# Back.net
KiCad netlist of a schematic drawn in Altium Designer
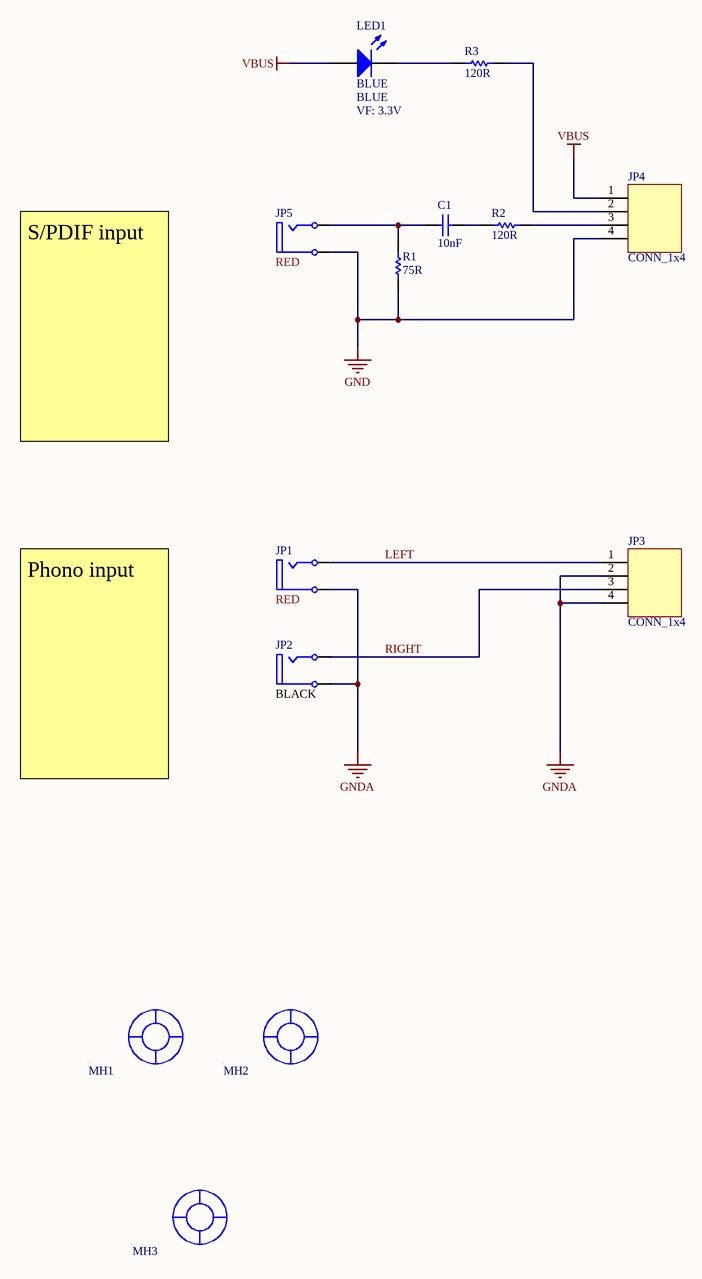
[diagram p0: Back.SchDoc]

(export (version "E")
  (design (tool "Eeschema 10.0.6"))
  (components
    (comp (ref "C1")
      (value "10nF")
      (footprint "CAPC0805(2012)145_N")
      (description "CAP 10nF 16V ±20% 0805 (2012 Metric) Thickness 1.45mm SMD")
      (fields (field (name "TOLERANCE") "Â±20%") (field (name "Comment") "CAP 10nF 16V 0805(2012)"))
      (libsource (lib "Altium Content Vault") (part "CAP"))
    )
    (comp (ref "JP1")
      (value "RED")
      (footprint "CONN_RCA-Lumberg-BTOR")
      (description "RCA panel-mount socket red, 1553 02 rot, Lumberg Connect GmbH")
      (fields (field (name "MPN") "BTOR 1 ROT") (field (name "Comment") "RCA RED"))
      (libsource (lib "micun") (part "CONN_RCA_LUMBERG_BTOR_1_RED"))
    )
    (comp (ref "JP2")
      (value "BLACK")
      (footprint "CONN_RCA-Lumberg-BTOR")
      (description "RCA panel-mount socket red, 1553 02 rot, Lumberg Connect GmbH")
      (fields (field (name "MPN") "BTOR 1 SCHWARZ") (field (name "Comment") "RCA BLACK"))
      (libsource (lib "micun") (part "CONN_RCA_LUMBERG_BTOR_1_BLACK"))
    )
    (comp (ref "JP3")
      (value "CONN_1x4")
      (footprint "CONN_HDR1X4-No3D")
      (description "Header, 4-Pin")
      (fields (field (name "MPN") "0470531000") (field (name "PUBLISHER") "Altium Limited"))
      (libsource (lib "micun") (part "CONN_MHDR_1x4"))
    )
    (comp (ref "JP4")
      (value "CONN_1x4")
      (footprint "CONN_HDR1X4-No3D")
      (description "Header, 4-Pin")
      (fields (field (name "MPN") "0470531000") (field (name "PUBLISHER") "Altium Limited"))
      (libsource (lib "micun") (part "CONN_MHDR_1x4"))
    )
    (comp (ref "JP5")
      (value "RED")
      (footprint "CONN_RCA-Lumberg-BTOR")
      (description "RCA panel-mount socket red, 1553 02 rot, Lumberg Connect GmbH")
      (fields (field (name "MPN") "BTOR 1 ROT") (field (name "Comment") "RCA RED"))
      (libsource (lib "micun") (part "CONN_RCA_LUMBERG_BTOR_1_RED"))
    )
    (comp (ref "LED1")
      (value "BLUE")
      (footprint "LED-KPTL-3216QBC")
      (description "LED BLUE")
      (fields
        (field (name "MPN") "KPTL-3216QBC-D-01")
        (field (name "ALTIUM_VALUE") "BLUE")
        (field (name "VF") "3.3V")
      )
      (libsource (lib "micun") (part "LED-BLUE-KPTL-3216QBC-D-01"))
    )
    (comp (ref "MH1")
      (value "Mounting hole")
      (footprint "MECH_MHOLE_3.5-GND")
      (libsource (lib "micun") (part "MECH_MHOLE"))
    )
    (comp (ref "MH2")
      (value "Mounting hole")
      (footprint "MECH_MHOLE_3.5")
      (libsource (lib "micun") (part "MECH_MHOLE"))
    )
    (comp (ref "MH3")
      (value "Mounting hole")
      (footprint "MECH_USB_MICRO_CUTOUT")
      (libsource (lib "micun") (part "MECH_MICRO_B_CUTOUT"))
    )
    (comp (ref "R1")
      (value "75R")
      (footprint "RESC0805(2012)_M")
      (description "75R 0.125W 1% 0805 (2012 Metric)  SMD")
      (fields (field (name "TOLERANCE") "1 %") (field (name "POWER") "0.125 W"))
      (libsource (lib "Altium Content Vault") (part "RES"))
    )
    (comp (ref "R2")
      (value "120R")
      (footprint "RESC0805(2012)_N")
      (description "120R 0.125W 5% 0805 (2012 Metric)  SMD")
      (fields (field (name "TOLERANCE") "5 %") (field (name "POWER") "0.125 W"))
      (libsource (lib "Altium Content Vault") (part "RES"))
    )
    (comp (ref "R3")
      (value "120R")
      (footprint "RESC0805(2012)_N")
      (description "120R 0.125W 5% 0805 (2012 Metric)  SMD")
      (fields (field (name "TOLERANCE") "5 %") (field (name "POWER") "0.125 W"))
      (libsource (lib "Altium Content Vault") (part "RES"))
    )
  )
  (nets
    (net (code "1") (name "/LEFT") (class "Default")
      (node (ref "JP1") (pin "1") (pinfunction "Signal_1") (pintype "passive"))
      (node (ref "JP3") (pin "1") (pinfunction "1_1") (pintype "passive"))
    )
    (net (code "2") (name "/RIGHT") (class "Default")
      (node (ref "JP2") (pin "1") (pinfunction "Signal_1") (pintype "passive"))
      (node (ref "JP3") (pin "3") (pinfunction "3_3") (pintype "passive"))
    )
    (net (code "3") (name "GND") (class "Default")
      (node (ref "JP4") (pin "4") (pinfunction "4_4") (pintype "passive"))
      (node (ref "JP5") (pin "2") (pinfunction "Ground_2") (pintype "power_in"))
      (node (ref "R1") (pin "2") (pinfunction "2_2") (pintype "passive"))
    )
    (net (code "4") (name "GNDA") (class "Default")
      (node (ref "JP1") (pin "2") (pinfunction "Ground_2") (pintype "power_in"))
      (node (ref "JP2") (pin "2") (pinfunction "Ground_2") (pintype "power_in"))
      (node (ref "JP3") (pin "2") (pinfunction "2_2") (pintype "passive"))
      (node (ref "JP3") (pin "4") (pinfunction "4_4") (pintype "passive"))
    )
    (net (code "5") (name "Net-(C1-Pad1)") (class "Default")
      (node (ref "C1") (pin "1") (pinfunction "1_1") (pintype "passive"))
      (node (ref "R2") (pin "2") (pinfunction "2_2") (pintype "passive"))
    )
    (net (code "6") (name "Net-(JP4-Pad2)") (class "Default")
      (node (ref "JP4") (pin "2") (pinfunction "2_2") (pintype "passive"))
      (node (ref "R3") (pin "1") (pinfunction "1_1") (pintype "passive"))
    )
    (net (code "7") (name "Net-(JP4-Pad3)") (class "Default")
      (node (ref "JP4") (pin "3") (pinfunction "3_3") (pintype "passive"))
      (node (ref "R2") (pin "1") (pinfunction "1_1") (pintype "passive"))
    )
    (net (code "8") (name "Net-(JP5-Signal)") (class "Default")
      (node (ref "C1") (pin "2") (pinfunction "2_2") (pintype "passive"))
      (node (ref "JP5") (pin "1") (pinfunction "Signal_1") (pintype "passive"))
      (node (ref "R1") (pin "1") (pinfunction "1_1") (pintype "passive"))
    )
    (net (code "9") (name "Net-(LED1-PadK)") (class "Default")
      (node (ref "LED1") (pin "K") (pinfunction "K_K") (pintype "passive"))
      (node (ref "R3") (pin "2") (pinfunction "2_2") (pintype "passive"))
    )
    (net (code "10") (name "VBUS") (class "Default")
      (node (ref "JP4") (pin "1") (pinfunction "1_1") (pintype "passive"))
      (node (ref "LED1") (pin "A") (pinfunction "A_A") (pintype "passive"))
    )
  )
)
